# USB_Sheet_ATmega8U2-MU.net
KiCad netlist of a schematic drawn in Altium Designer
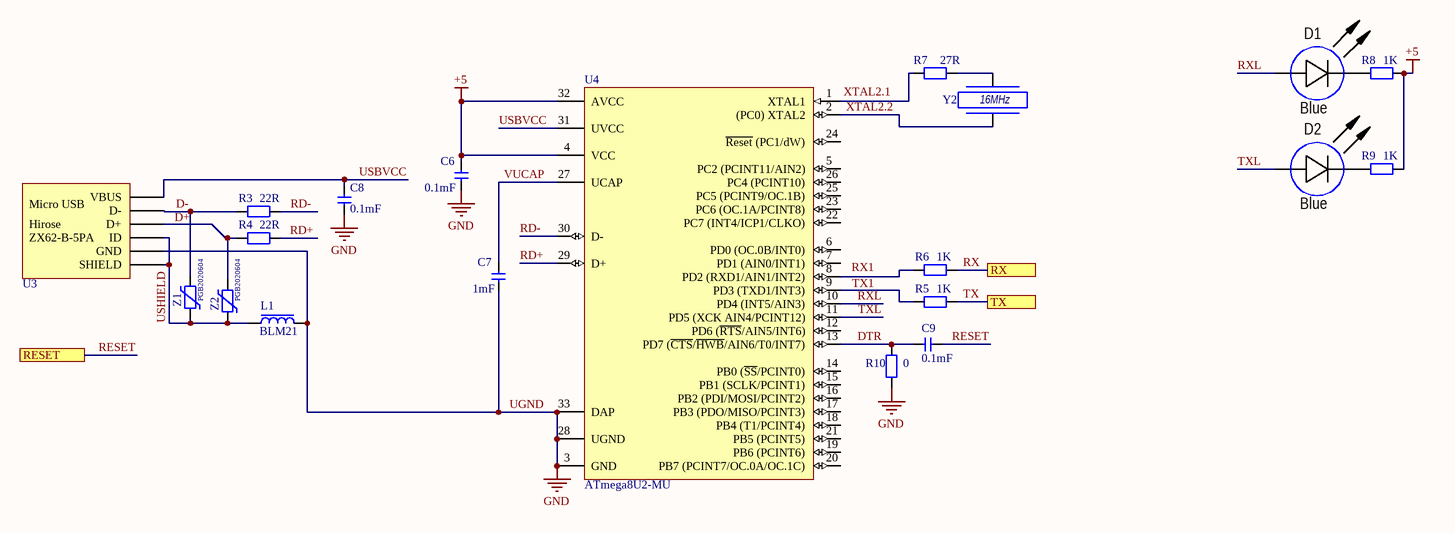
[diagram p0: USB Sheet (ATmega8U2-MU).SchDoc]

(export (version "E")
  (design (tool "Eeschema 10.0.6"))
  (components
    (comp (ref "C6")
      (value "0.1mF")
      (footprint "cap0603")
      (libsource (lib "AlexChistiakov") (part "Cap SMD"))
    )
    (comp (ref "C7") (value "1mF") (footprint "cap0603") (libsource (lib "AlexChistiakov") (part "Cap SMD")))
    (comp (ref "C8")
      (value "0.1mF")
      (footprint "cap0603")
      (libsource (lib "AlexChistiakov") (part "Cap SMD"))
    )
    (comp (ref "C9")
      (value "0.1mF")
      (footprint "cap0603")
      (libsource (lib "AlexChistiakov") (part "Cap SMD"))
    )
    (comp (ref "D1") (value "Blue") (footprint "standard:CH0805LB") (libsource (lib "Discrete") (part "LED")))
    (comp (ref "D2") (value "Blue") (footprint "standard:CH0805LB") (libsource (lib "Discrete") (part "LED")))
    (comp (ref "L1")
      (value "BLM21")
      (footprint "res0805")
      (libsource (lib "AlexChistiakov") (part "Drossel"))
    )
    (comp (ref "R3")
      (value "22R")
      (footprint "res0603")
      (libsource (lib "AlexChistiakov") (part "Resistor SMD"))
    )
    (comp (ref "R4")
      (value "22R")
      (footprint "res0603")
      (libsource (lib "AlexChistiakov") (part "Resistor SMD"))
    )
    (comp (ref "R5")
      (value "1K")
      (footprint "res0603")
      (libsource (lib "AlexChistiakov") (part "Resistor SMD"))
    )
    (comp (ref "R6")
      (value "1K")
      (footprint "res0603")
      (libsource (lib "AlexChistiakov") (part "Resistor SMD"))
    )
    (comp (ref "R7")
      (value "27R")
      (footprint "res0603")
      (libsource (lib "AlexChistiakov") (part "Resistor SMD"))
    )
    (comp (ref "R8")
      (value "1K")
      (footprint "res0603")
      (libsource (lib "AlexChistiakov") (part "Resistor SMD"))
    )
    (comp (ref "R9")
      (value "1K")
      (footprint "res0603")
      (libsource (lib "AlexChistiakov") (part "Resistor SMD"))
    )
    (comp (ref "R10")
      (value "0")
      (footprint "res0603")
      (libsource (lib "AlexChistiakov") (part "Resistor SMD"))
    )
    (comp (ref "U3")
      (value "ZX62-B-5PA")
      (footprint "ZX62-B-5PA")
      (libsource (lib "AlexChistiakov") (part "ZX62-B-5PA"))
    )
    (comp (ref "U4")
      (value "ATmega8U2-MU")
      (footprint "32PG_N")
      (fields (field (name "PUBLISHER") "Altium Limited"))
      (libsource (lib "Atmel Microcontroller 8-Bit megaAVR") (part "ATmega8U2-MU"))
    )
    (comp (ref "Y2")
      (value "16MHz")
      (footprint "QSMD5.0x3.2x1.0")
      (description "Кварцевый резонатор")
      (libsource (lib "TarabusLib_KOR") (part "Crystal"))
    )
    (comp (ref "Z1")
      (value "PGB2020604")
      (footprint "res0603")
      (libsource (lib "AlexChistiakov") (part "Varistor"))
    )
    (comp (ref "Z2")
      (value "PGB2020604")
      (footprint "res0603")
      (libsource (lib "AlexChistiakov") (part "Varistor"))
    )
  )
  (nets
    (net (code "1") (name "+5") (class "Default")
      (node (ref "C6") (pin "2") (pinfunction "2_2") (pintype "passive"))
      (node (ref "R8") (pin "2") (pinfunction "2_2") (pintype "passive"))
      (node (ref "R9") (pin "2") (pinfunction "2_2") (pintype "passive"))
      (node (ref "U4") (pin "32") (pinfunction "AVCC_32") (pintype "power_in"))
      (node (ref "U4") (pin "4") (pinfunction "VCC_4") (pintype "power_in"))
    )
    (net (code "3") (name "/D-") (class "Default")
      (node (ref "R3") (pin "1") (pinfunction "1_1") (pintype "passive"))
      (node (ref "U3") (pin "2") (pinfunction "D-_2") (pintype "passive"))
      (node (ref "Z1") (pin "2") (pinfunction "2_2") (pintype "passive"))
    )
    (net (code "4") (name "/DTR") (class "Default")
      (node (ref "C9") (pin "1") (pinfunction "1_1") (pintype "passive"))
      (node (ref "R10") (pin "2") (pinfunction "2_2") (pintype "passive"))
      (node (ref "U4") (pin "13") (pinfunction "PD7_(~{CTS}/~{HWB}/AIN6/T0/INT7)_13") (pintype "bidirectional"))
    )
    (net (code "5") (name "/RD+") (class "Default")
      (node (ref "R4") (pin "2") (pinfunction "2_2") (pintype "passive"))
      (node (ref "U4") (pin "29") (pinfunction "D+_29") (pintype "bidirectional"))
    )
    (net (code "6") (name "/RD-") (class "Default")
      (node (ref "R3") (pin "2") (pinfunction "2_2") (pintype "passive"))
      (node (ref "U4") (pin "30") (pinfunction "D-_30") (pintype "bidirectional"))
    )
    (net (code "7") (name "/RESET") (class "Default")
      (node (ref "C9") (pin "2") (pinfunction "2_2") (pintype "passive"))
    )
    (net (code "8") (name "/RX") (class "Default")
      (node (ref "R6") (pin "2") (pinfunction "2_2") (pintype "passive"))
    )
    (net (code "10") (name "/RXL") (class "Default")
      (node (ref "D1") (pin "1") (pinfunction "A_1") (pintype "passive"))
      (node (ref "U4") (pin "10") (pinfunction "PD4_(INT5/AIN3)_10") (pintype "bidirectional"))
    )
    (net (code "11") (name "/TX") (class "Default")
      (node (ref "R5") (pin "2") (pinfunction "2_2") (pintype "passive"))
    )
    (net (code "13") (name "/TXL") (class "Default")
      (node (ref "D2") (pin "1") (pinfunction "A_1") (pintype "passive"))
      (node (ref "U4") (pin "11") (pinfunction "PD5_(XCK_AIN4/PCINT12)_11") (pintype "bidirectional"))
    )
    (net (code "14") (name "/USBVCC") (class "Default")
      (node (ref "C8") (pin "2") (pinfunction "2_2") (pintype "passive"))
      (node (ref "U3") (pin "1") (pinfunction "VBUS_1") (pintype "passive"))
      (node (ref "U4") (pin "31") (pinfunction "UVCC_31") (pintype "power_in"))
    )
    (net (code "15") (name "/USHIELD") (class "Default")
      (node (ref "L1") (pin "1") (pinfunction "1_1") (pintype "passive"))
      (node (ref "U3") (pin "4") (pinfunction "ID_4") (pintype "passive"))
      (node (ref "U3") (pin "6") (pinfunction "SHIELD_6") (pintype "passive"))
      (node (ref "Z1") (pin "1") (pinfunction "1_1") (pintype "passive"))
      (node (ref "Z2") (pin "1") (pinfunction "1_1") (pintype "passive"))
    )
    (net (code "16") (name "/VUCAP") (class "Default")
      (node (ref "C7") (pin "2") (pinfunction "2_2") (pintype "passive"))
      (node (ref "U4") (pin "27") (pinfunction "UCAP_27") (pintype "power_in"))
    )
    (net (code "18") (name "/XTAL2.2") (class "Default")
      (node (ref "U4") (pin "2") (pinfunction "(PC0)_XTAL2_2") (pintype "bidirectional"))
      (node (ref "Y2") (pin "1") (pinfunction "1_1") (pintype "passive"))
    )
    (net (code "19") (name "GND") (class "Default")
      (node (ref "C6") (pin "1") (pinfunction "1_1") (pintype "passive"))
      (node (ref "C7") (pin "1") (pinfunction "1_1") (pintype "passive"))
      (node (ref "C8") (pin "1") (pinfunction "1_1") (pintype "passive"))
      (node (ref "L1") (pin "2") (pinfunction "2_2") (pintype "passive"))
      (node (ref "R10") (pin "1") (pinfunction "1_1") (pintype "passive"))
      (node (ref "U3") (pin "5") (pinfunction "GND_5") (pintype "passive"))
      (node (ref "U4") (pin "28") (pinfunction "UGND_28") (pintype "power_in"))
      (node (ref "U4") (pin "3") (pinfunction "GND_3") (pintype "power_in"))
      (node (ref "U4") (pin "33") (pinfunction "DAP_33") (pintype "power_in"))
    )
    (net (code "20") (name "Net-(D1-C)") (class "Default")
      (node (ref "D1") (pin "2") (pinfunction "C_2") (pintype "passive"))
      (node (ref "R8") (pin "1") (pinfunction "1_1") (pintype "passive"))
    )
    (net (code "21") (name "Net-(D2-C)") (class "Default")
      (node (ref "D2") (pin "2") (pinfunction "C_2") (pintype "passive"))
      (node (ref "R9") (pin "1") (pinfunction "1_1") (pintype "passive"))
    )
    (net (code "22") (name "Net-(R7-Pad2)") (class "Default")
      (node (ref "R7") (pin "2") (pinfunction "2_2") (pintype "passive"))
      (node (ref "Y2") (pin "2") (pinfunction "2_2") (pintype "passive"))
    )
    (net (code "23") (name "Net-(U3-D+)") (class "Default")
      (node (ref "R4") (pin "1") (pinfunction "1_1") (pintype "passive"))
      (node (ref "U3") (pin "3") (pinfunction "D+_3") (pintype "passive"))
      (node (ref "Z2") (pin "2") (pinfunction "2_2") (pintype "passive"))
    )
    (net (code "24") (name "Net-(U4-PD2_(RXD1{slash}AIN1{slash}INT2))") (class "Default")
      (node (ref "R6") (pin "1") (pinfunction "1_1") (pintype "passive"))
      (node (ref "U4") (pin "8") (pinfunction "PD2_(RXD1/AIN1/INT2)_8") (pintype "bidirectional"))
    )
    (net (code "25") (name "Net-(U4-PD3_(TXD1{slash}INT3))") (class "Default")
      (node (ref "R5") (pin "1") (pinfunction "1_1") (pintype "passive"))
      (node (ref "U4") (pin "9") (pinfunction "PD3_(TXD1/INT3)_9") (pintype "bidirectional"))
    )
    (net (code "26") (name "Net-(U4-XTAL1)") (class "Default")
      (node (ref "R7") (pin "1") (pinfunction "1_1") (pintype "passive"))
      (node (ref "U4") (pin "1") (pinfunction "XTAL1_1") (pintype "input"))
    )
    (net (code "27") (name "unconnected-(U4-PB0_(~{SS}{slash}PCINT0)-Pad14)") (class "Default")
      (node (ref "U4") (pin "14") (pinfunction "PB0_(~{SS}/PCINT0)_14") (pintype "bidirectional"))
    )
    (net (code "28") (name "unconnected-(U4-PB1_(SCLK{slash}PCINT1)-Pad15)") (class "Default")
      (node (ref "U4") (pin "15") (pinfunction "PB1_(SCLK/PCINT1)_15") (pintype "bidirectional"))
    )
    (net (code "29") (name "unconnected-(U4-PB2_(PDI{slash}MOSI{slash}PCINT2)-Pad16)") (class "Default")
      (node (ref "U4") (pin "16") (pinfunction "PB2_(PDI/MOSI/PCINT2)_16") (pintype "bidirectional"))
    )
    (net (code "30") (name "unconnected-(U4-PB3_(PDO{slash}MISO{slash}PCINT3)-Pad17)") (class "Default")
      (node (ref "U4") (pin "17") (pinfunction "PB3_(PDO/MISO/PCINT3)_17") (pintype "bidirectional"))
    )
    (net (code "31") (name "unconnected-(U4-PB4_(T1{slash}PCINT4)-Pad18)") (class "Default")
      (node (ref "U4") (pin "18") (pinfunction "PB4_(T1/PCINT4)_18") (pintype "bidirectional"))
    )
    (net (code "32") (name "unconnected-(U4-PB5_(PCINT5)-Pad21)") (class "Default")
      (node (ref "U4") (pin "21") (pinfunction "PB5_(PCINT5)_21") (pintype "bidirectional"))
    )
    (net (code "33") (name "unconnected-(U4-PB6_(PCINT6)-Pad19)") (class "Default")
      (node (ref "U4") (pin "19") (pinfunction "PB6_(PCINT6)_19") (pintype "bidirectional"))
    )
    (net (code "34") (name "unconnected-(U4-PB7_(PCINT7{slash}OC.0A{slash}OC.1C)-Pad20)") (class "Default")
      (node (ref "U4") (pin "20") (pinfunction "PB7_(PCINT7/OC.0A/OC.1C)_20") (pintype "bidirectional"))
    )
    (net (code "35") (name "unconnected-(U4-PC2_(PCINT11{slash}AIN2)-Pad5)") (class "Default")
      (node (ref "U4") (pin "5") (pinfunction "PC2_(PCINT11/AIN2)_5") (pintype "bidirectional"))
    )
    (net (code "36") (name "unconnected-(U4-PC4_(PCINT10)-Pad26)") (class "Default")
      (node (ref "U4") (pin "26") (pinfunction "PC4_(PCINT10)_26") (pintype "bidirectional"))
    )
    (net (code "37") (name "unconnected-(U4-PC5_(PCINT9{slash}OC.1B)-Pad25)") (class "Default")
      (node (ref "U4") (pin "25") (pinfunction "PC5_(PCINT9/OC.1B)_25") (pintype "bidirectional"))
    )
    (net (code "38") (name "unconnected-(U4-PC6_(OC.1A{slash}PCINT8)-Pad23)") (class "Default")
      (node (ref "U4") (pin "23") (pinfunction "PC6_(OC.1A/PCINT8)_23") (pintype "bidirectional"))
    )
    (net (code "39") (name "unconnected-(U4-PC7_(INT4{slash}ICP1{slash}CLKO)-Pad22)") (class "Default")
      (node (ref "U4") (pin "22") (pinfunction "PC7_(INT4/ICP1/CLKO)_22") (pintype "bidirectional"))
    )
    (net (code "40") (name "unconnected-(U4-PD0_(OC.0B{slash}INT0)-Pad6)") (class "Default")
      (node (ref "U4") (pin "6") (pinfunction "PD0_(OC.0B/INT0)_6") (pintype "bidirectional"))
    )
    (net (code "41") (name "unconnected-(U4-PD1_(AIN0{slash}INT1)-Pad7)") (class "Default")
      (node (ref "U4") (pin "7") (pinfunction "PD1_(AIN0/INT1)_7") (pintype "bidirectional"))
    )
    (net (code "42") (name "unconnected-(U4-PD6_(~{RTS}{slash}AIN5{slash}INT6)-Pad12)") (class "Default")
      (node (ref "U4") (pin "12") (pinfunction "PD6_(~{RTS}/AIN5/INT6)_12") (pintype "bidirectional"))
    )
    (net (code "43") (name "unconnected-(U4-~{Reset}_(PC1{slash}dW)-Pad24)") (class "Default")
      (node (ref "U4") (pin "24") (pinfunction "~{Reset}_(PC1/dW)_24") (pintype "bidirectional"))
    )
  )
)
